# main.net
KiCad netlist of a schematic drawn in EAGLE
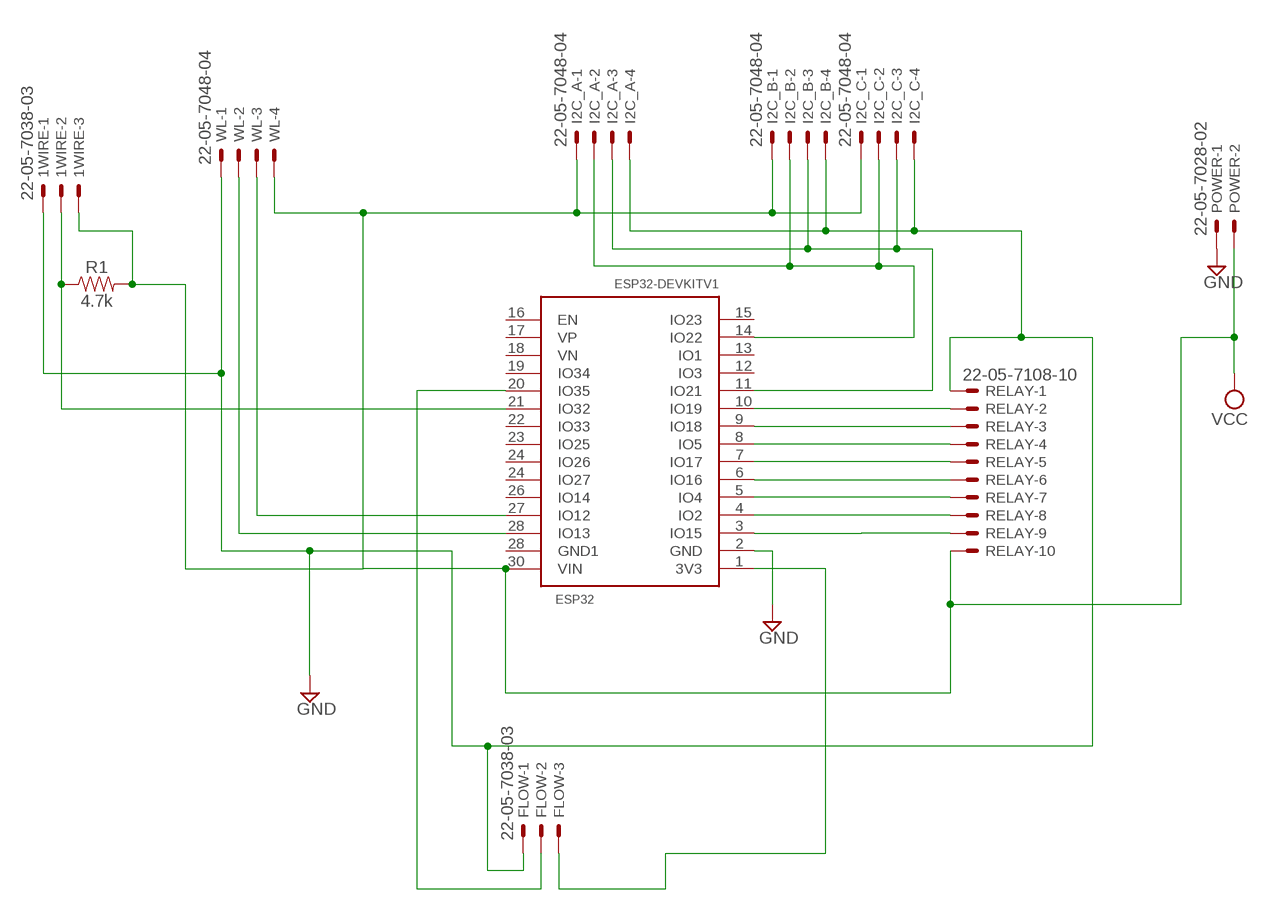
[diagram p0: schematic, sheet 1]

(export (version "E")
  (design (tool "Eeschema 10.0.6"))
  (components
    (comp (ref "1WIRE")
      (value "22-05-7038-03")
      (footprint "eagle-import:7395-03")
      (fields (field (name "MF") "MOLEX"))
      (libsource (lib "eagle-import") (part "22-?-0305-7038"))
    )
    (comp (ref "ESP32")
      (value "ESP32DEVKITV1")
      (footprint "eagle-import:ESP32-DEVKITV1")
      (libsource (lib "eagle-import") (part "ESP32DEVKITV1"))
    )
    (comp (ref "FLOW")
      (value "22-05-7038-03")
      (footprint "eagle-import:7395-03")
      (fields (field (name "MF") "MOLEX"))
      (libsource (lib "eagle-import") (part "22-?-0305-7038"))
    )
    (comp (ref "I2C_A")
      (value "22-05-7048-04")
      (footprint "eagle-import:7395-04")
      (fields (field (name "MF") "MOLEX"))
      (libsource (lib "eagle-import") (part "22-?-0405-7048"))
    )
    (comp (ref "I2C_B")
      (value "22-05-7048-04")
      (footprint "eagle-import:7395-04")
      (fields (field (name "MF") "MOLEX"))
      (libsource (lib "eagle-import") (part "22-?-0405-7048"))
    )
    (comp (ref "I2C_C")
      (value "22-05-7048-04")
      (footprint "eagle-import:7395-04")
      (fields (field (name "MF") "MOLEX"))
      (libsource (lib "eagle-import") (part "22-?-0405-7048"))
    )
    (comp (ref "POWER")
      (value "22-05-7028-02")
      (footprint "eagle-import:7395-02")
      (fields (field (name "MF") "MOLEX"))
      (libsource (lib "eagle-import") (part "22-?-0205-7028"))
    )
    (comp (ref "R1")
      (value "4.7k")
      (footprint "eagle-import:0603")
      (libsource (lib "eagle-import") (part "4.7KOHM-0603-1/10W-1%"))
    )
    (comp (ref "RELAY")
      (value "22-05-7108-10")
      (footprint "eagle-import:7395-10")
      (fields (field (name "MF") "MOLEX"))
      (libsource (lib "eagle-import") (part "22-?-1005-7108"))
    )
    (comp (ref "WL")
      (value "22-05-7048-04")
      (footprint "eagle-import:7395-04")
      (fields (field (name "MF") "MOLEX"))
      (libsource (lib "eagle-import") (part "22-?-0405-7048"))
    )
  )
  (nets
    (net (code "1") (name "GND") (class "Default")
      (node (ref "1WIRE") (pin "1") (pinfunction "S_1") (pintype "passive"))
      (node (ref "ESP32") (pin "2") (pinfunction "GND_2") (pintype "bidirectional"))
      (node (ref "FLOW") (pin "1") (pinfunction "S_1") (pintype "passive"))
      (node (ref "I2C_A") (pin "4") (pinfunction "S_4") (pintype "passive"))
      (node (ref "I2C_B") (pin "4") (pinfunction "S_4") (pintype "passive"))
      (node (ref "I2C_C") (pin "4") (pinfunction "S_4") (pintype "passive"))
      (node (ref "POWER") (pin "1") (pinfunction "S_1") (pintype "passive"))
      (node (ref "RELAY") (pin "1") (pinfunction "S_1") (pintype "passive"))
      (node (ref "WL") (pin "1") (pinfunction "S_1") (pintype "passive"))
    )
    (net (code "2") (name "Net-(1WIREB-S)") (class "Default")
      (node (ref "1WIRE") (pin "2") (pinfunction "S_2") (pintype "passive"))
      (node (ref "ESP32") (pin "21") (pinfunction "IO32_21") (pintype "bidirectional"))
      (node (ref "R1") (pin "1") (pinfunction "1_1") (pintype "passive"))
    )
    (net (code "3") (name "Net-(ESP32-3V3)") (class "Default")
      (node (ref "ESP32") (pin "1") (pinfunction "3V3_1") (pintype "bidirectional"))
      (node (ref "FLOW") (pin "3") (pinfunction "S_3") (pintype "passive"))
    )
    (net (code "4") (name "Net-(ESP32-IO2)") (class "Default")
      (node (ref "ESP32") (pin "4") (pinfunction "IO2_4") (pintype "bidirectional"))
      (node (ref "RELAY") (pin "8") (pinfunction "S_8") (pintype "passive"))
    )
    (net (code "5") (name "Net-(ESP32-IO4)") (class "Default")
      (node (ref "ESP32") (pin "5") (pinfunction "IO4_5") (pintype "bidirectional"))
      (node (ref "RELAY") (pin "7") (pinfunction "S_7") (pintype "passive"))
    )
    (net (code "6") (name "Net-(ESP32-IO5)") (class "Default")
      (node (ref "ESP32") (pin "8") (pinfunction "IO5_8") (pintype "bidirectional"))
      (node (ref "RELAY") (pin "4") (pinfunction "S_4") (pintype "passive"))
    )
    (net (code "7") (name "Net-(ESP32-IO12)") (class "Default")
      (node (ref "ESP32") (pin "27") (pinfunction "IO12_27") (pintype "bidirectional"))
      (node (ref "WL") (pin "3") (pinfunction "S_3") (pintype "passive"))
    )
    (net (code "8") (name "Net-(ESP32-IO13)") (class "Default")
      (node (ref "ESP32") (pin "28") (pinfunction "IO13_28") (pintype "bidirectional"))
      (node (ref "WL") (pin "2") (pinfunction "S_2") (pintype "passive"))
    )
    (net (code "9") (name "Net-(ESP32-IO15)") (class "Default")
      (node (ref "ESP32") (pin "3") (pinfunction "IO15_3") (pintype "bidirectional"))
      (node (ref "RELAY") (pin "9") (pinfunction "S_9") (pintype "passive"))
    )
    (net (code "10") (name "Net-(ESP32-IO16)") (class "Default")
      (node (ref "ESP32") (pin "6") (pinfunction "IO16_6") (pintype "bidirectional"))
      (node (ref "RELAY") (pin "6") (pinfunction "S_6") (pintype "passive"))
    )
    (net (code "11") (name "Net-(ESP32-IO17)") (class "Default")
      (node (ref "ESP32") (pin "7") (pinfunction "IO17_7") (pintype "bidirectional"))
      (node (ref "RELAY") (pin "5") (pinfunction "S_5") (pintype "passive"))
    )
    (net (code "12") (name "Net-(ESP32-IO18)") (class "Default")
      (node (ref "ESP32") (pin "9") (pinfunction "IO18_9") (pintype "bidirectional"))
      (node (ref "RELAY") (pin "3") (pinfunction "S_3") (pintype "passive"))
    )
    (net (code "13") (name "Net-(ESP32-IO19)") (class "Default")
      (node (ref "ESP32") (pin "10") (pinfunction "IO19_10") (pintype "bidirectional"))
      (node (ref "RELAY") (pin "2") (pinfunction "S_2") (pintype "passive"))
    )
    (net (code "14") (name "Net-(ESP32-IO21)") (class "Default")
      (node (ref "ESP32") (pin "11") (pinfunction "IO21_11") (pintype "bidirectional"))
      (node (ref "I2C_A") (pin "3") (pinfunction "S_3") (pintype "passive"))
      (node (ref "I2C_B") (pin "3") (pinfunction "S_3") (pintype "passive"))
      (node (ref "I2C_C") (pin "3") (pinfunction "S_3") (pintype "passive"))
    )
    (net (code "15") (name "Net-(ESP32-IO22)") (class "Default")
      (node (ref "ESP32") (pin "14") (pinfunction "IO22_14") (pintype "bidirectional"))
      (node (ref "I2C_A") (pin "2") (pinfunction "S_2") (pintype "passive"))
      (node (ref "I2C_B") (pin "2") (pinfunction "S_2") (pintype "passive"))
      (node (ref "I2C_C") (pin "2") (pinfunction "S_2") (pintype "passive"))
    )
    (net (code "16") (name "Net-(ESP32-IO35)") (class "Default")
      (node (ref "ESP32") (pin "20") (pinfunction "IO35_20") (pintype "bidirectional"))
      (node (ref "FLOW") (pin "2") (pinfunction "S_2") (pintype "passive"))
    )
    (net (code "17") (name "VCC") (class "Default")
      (node (ref "1WIRE") (pin "3") (pinfunction "S_3") (pintype "passive"))
      (node (ref "ESP32") (pin "30") (pinfunction "VIN_30") (pintype "bidirectional"))
      (node (ref "I2C_A") (pin "1") (pinfunction "S_1") (pintype "passive"))
      (node (ref "I2C_B") (pin "1") (pinfunction "S_1") (pintype "passive"))
      (node (ref "I2C_C") (pin "1") (pinfunction "S_1") (pintype "passive"))
      (node (ref "POWER") (pin "2") (pinfunction "S_2") (pintype "passive"))
      (node (ref "R1") (pin "2") (pinfunction "2_2") (pintype "passive"))
      (node (ref "RELAY") (pin "10") (pinfunction "S_10") (pintype "passive"))
      (node (ref "WL") (pin "4") (pinfunction "S_4") (pintype "passive"))
    )
    (net (code "18") (name "unconnected-(ESP32-EN-Pad16)") (class "Default")
      (node (ref "ESP32") (pin "16") (pinfunction "EN_16") (pintype "bidirectional"))
    )
    (net (code "19") (name "unconnected-(ESP32-GND1-Pad28)") (class "Default")
      (node (ref "ESP32") (pin "28") (pinfunction "GND1_28") (pintype "bidirectional"))
    )
    (net (code "20") (name "unconnected-(ESP32-IO1-Pad13)") (class "Default")
      (node (ref "ESP32") (pin "13") (pinfunction "IO1_13") (pintype "bidirectional"))
    )
    (net (code "21") (name "unconnected-(ESP32-IO3-Pad12)") (class "Default")
      (node (ref "ESP32") (pin "12") (pinfunction "IO3_12") (pintype "bidirectional"))
    )
    (net (code "22") (name "unconnected-(ESP32-IO14-Pad26)") (class "Default")
      (node (ref "ESP32") (pin "26") (pinfunction "IO14_26") (pintype "bidirectional"))
    )
    (net (code "23") (name "unconnected-(ESP32-IO23-Pad15)") (class "Default")
      (node (ref "ESP32") (pin "15") (pinfunction "IO23_15") (pintype "bidirectional"))
    )
    (net (code "24") (name "unconnected-(ESP32-IO25-Pad23)") (class "Default")
      (node (ref "ESP32") (pin "23") (pinfunction "IO25_23") (pintype "bidirectional"))
    )
    (net (code "25") (name "unconnected-(ESP32-IO26-Pad24)") (class "Default")
      (node (ref "ESP32") (pin "24") (pinfunction "IO26_24") (pintype "bidirectional"))
    )
    (net (code "26") (name "unconnected-(ESP32-IO27-Pad24)") (class "Default")
      (node (ref "ESP32") (pin "24") (pinfunction "IO27_24") (pintype "bidirectional"))
    )
    (net (code "27") (name "unconnected-(ESP32-IO33-Pad22)") (class "Default")
      (node (ref "ESP32") (pin "22") (pinfunction "IO33_22") (pintype "bidirectional"))
    )
    (net (code "28") (name "unconnected-(ESP32-IO34-Pad19)") (class "Default")
      (node (ref "ESP32") (pin "19") (pinfunction "IO34_19") (pintype "bidirectional"))
    )
    (net (code "29") (name "unconnected-(ESP32-VN-Pad18)") (class "Default")
      (node (ref "ESP32") (pin "18") (pinfunction "VN_18") (pintype "bidirectional"))
    )
    (net (code "30") (name "unconnected-(ESP32-VP-Pad17)") (class "Default")
      (node (ref "ESP32") (pin "17") (pinfunction "VP_17") (pintype "bidirectional"))
    )
  )
)
